# LowduinoPTH_ZIF.net
KiCad netlist of a schematic drawn in EAGLE
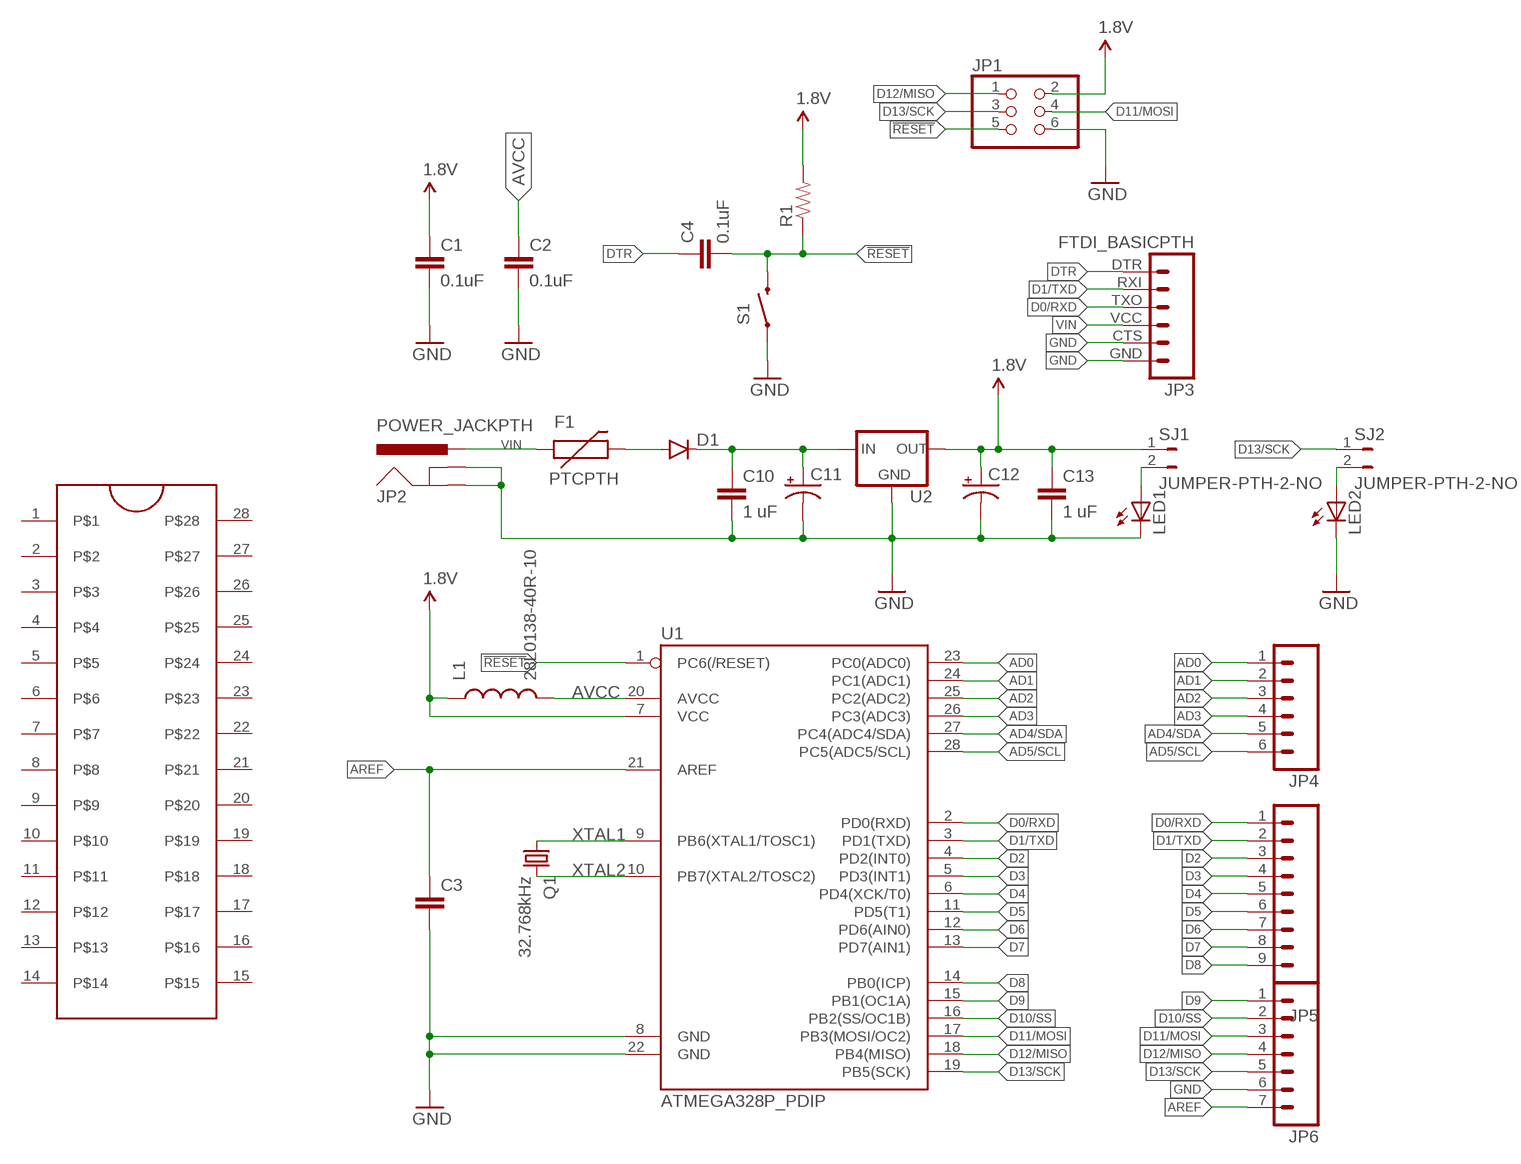
[diagram p0: schematic, sheet 1]

(export (version "E")
  (design (tool "Eeschema 10.0.6"))
  (components
    (comp (ref "C1")
      (value "0.1uF")
      (footprint "eagle-import:CAP-PTH-SMALL2")
      (libsource (lib "eagle-import") (part "CAPPTH2"))
    )
    (comp (ref "C2")
      (value "0.1uF")
      (footprint "eagle-import:CAP-PTH-5MM")
      (libsource (lib "eagle-import") (part "SparkFun-Passives_CAPPTH1"))
    )
    (comp (ref "C3")
      (value "CAPPTH2")
      (footprint "eagle-import:CAP-PTH-SMALL2")
      (libsource (lib "eagle-import") (part "CAPPTH2"))
    )
    (comp (ref "C4")
      (value "0.1uF")
      (footprint "eagle-import:CAP-PTH-SMALL2")
      (libsource (lib "eagle-import") (part "SparkFun-Passives_CAPPTH2"))
    )
    (comp (ref "C10")
      (value "1 uF")
      (footprint "eagle-import:CAP-PTH-SMALL2")
      (libsource (lib "eagle-import") (part "CAPPTH2"))
    )
    (comp (ref "C11")
      (value "CPOL-USE2.5-6")
      (footprint "eagle-import:E2,5-6")
      (libsource (lib "eagle-import") (part "CPOL-USE2.5-6"))
    )
    (comp (ref "C12")
      (value "CPOL-USE2.5-6")
      (footprint "eagle-import:E2,5-6")
      (libsource (lib "eagle-import") (part "CPOL-USE2.5-6"))
    )
    (comp (ref "C13")
      (value "1 uF")
      (footprint "eagle-import:CAP-PTH-SMALL2")
      (libsource (lib "eagle-import") (part "CAPPTH2"))
    )
    (comp (ref "D1")
      (value "DIODEPTH")
      (footprint "eagle-import:DIODE-1N4001")
      (libsource (lib "eagle-import") (part "DIODEPTH"))
    )
    (comp (ref "F1")
      (value "PTCPTH")
      (footprint "eagle-import:PTC")
      (libsource (lib "eagle-import") (part "PTCPTH"))
    )
    (comp (ref "JP1")
      (value "PINHD-2X3")
      (footprint "eagle-import:2X03")
      (libsource (lib "eagle-import") (part "PINHD-2X3"))
    )
    (comp (ref "JP2")
      (value "POWER_JACKPTH")
      (footprint "eagle-import:POWER_JACK_PTH")
      (libsource (lib "eagle-import") (part "POWER_JACKPTH"))
    )
    (comp (ref "JP3")
      (value "FTDI_BASICPTH")
      (footprint "eagle-import:FTDI_BASIC")
      (libsource (lib "eagle-import") (part "FTDI_BASICPTH"))
    )
    (comp (ref "JP4")
      (value "M06SILK_FEMALE_PTH")
      (footprint "eagle-import:1X06")
      (libsource (lib "eagle-import") (part "M06SILK_FEMALE_PTH"))
    )
    (comp (ref "JP5")
      (value "M09")
      (footprint "eagle-import:1X09")
      (libsource (lib "eagle-import") (part "M09"))
    )
    (comp (ref "JP6")
      (value "M07")
      (footprint "eagle-import:1X07")
      (libsource (lib "eagle-import") (part "M07"))
    )
    (comp (ref "L1")
      (value "28L0138-40R-10")
      (footprint "eagle-import:AXIAL-0.6")
      (libsource (lib "eagle-import") (part "INDUCTORAXIAL-0.6"))
    )
    (comp (ref "LED1")
      (value "LED3MM")
      (footprint "eagle-import:LED3MM")
      (libsource (lib "eagle-import") (part "LED3MM"))
    )
    (comp (ref "LED2")
      (value "LED3MM")
      (footprint "eagle-import:LED3MM")
      (libsource (lib "eagle-import") (part "LED3MM"))
    )
    (comp (ref "Q1")
      (value "32.768kHz")
      (footprint "eagle-import:TC26V")
      (libsource (lib "eagle-import") (part "CRYSTALTC26V"))
    )
    (comp (ref "R1")
      (value "RESISTORPTH-1/4W-VERT")
      (footprint "eagle-import:AXIAL-0.1")
      (libsource (lib "eagle-import") (part "RESISTORPTH-1/4W-VERT"))
    )
    (comp (ref "S1")
      (value "SWITCH-MOMENTARY-2PTH")
      (footprint "eagle-import:TACTILE-PTH")
      (libsource (lib "eagle-import") (part "SWITCH-MOMENTARY-2PTH"))
    )
    (comp (ref "SJ1")
      (value "JUMPER-PTH-2-NO")
      (footprint "eagle-import:PTH-JUMPER-2-NO_NO_SILK")
      (libsource (lib "eagle-import") (part "JUMPER-PTH-2-NO"))
    )
    (comp (ref "SJ2")
      (value "JUMPER-PTH-2-NO")
      (footprint "eagle-import:PTH-JUMPER-2-NO_NO_SILK")
      (libsource (lib "eagle-import") (part "JUMPER-PTH-2-NO"))
    )
    (comp (ref "U$1")
      (value "ZIFSOCKET-28-3ZIFFSOCKET-28-3")
      (footprint "eagle-import:DIL28-3-ZIF_SOCKET")
      (libsource (lib "eagle-import") (part "ZIFSOCKET-28-3ZIFFSOCKET-28-3"))
    )
    (comp (ref "U1")
      (value "ATMEGA328P_PDIP")
      (footprint "eagle-import:DIL28-3")
      (libsource (lib "eagle-import") (part "ATMEGA328P_PDIP"))
    )
    (comp (ref "U2")
      (value "V_REG_78XXTO-92_UNTESTED")
      (footprint "eagle-import:TO-92")
      (libsource (lib "eagle-import") (part "V_REG_78XXTO-92_UNTESTED"))
    )
  )
  (nets
    (net (code "1") (name "/XTAL1") (class "Default")
      (node (ref "Q1") (pin "1") (pinfunction "1_1") (pintype "passive"))
      (node (ref "U1") (pin "9") (pinfunction "PB6(XTAL1/TOSC1)_9") (pintype "bidirectional"))
    )
    (net (code "2") (name "/XTAL2") (class "Default")
      (node (ref "Q1") (pin "2") (pinfunction "2_2") (pintype "passive"))
      (node (ref "U1") (pin "10") (pinfunction "PB7(XTAL2/TOSC2)_10") (pintype "bidirectional"))
    )
    (net (code "3") (name "/~{RESET}") (class "Default")
      (node (ref "C4") (pin "2") (pinfunction "2_2") (pintype "passive"))
      (node (ref "JP1") (pin "5") (pinfunction "5_5") (pintype "passive"))
      (node (ref "R1") (pin "P$1") (pinfunction "1_P$1") (pintype "passive"))
      (node (ref "S1") (pin "3") (pinfunction "2_3") (pintype "passive"))
      (node (ref "U1") (pin "1") (pinfunction "PC6(/RESET)_1") (pintype "bidirectional"))
    )
    (net (code "4") (name "1.8V") (class "Default")
      (node (ref "C1") (pin "1") (pinfunction "1_1") (pintype "passive"))
      (node (ref "C12") (pin "+") (pinfunction "+_+") (pintype "passive"))
      (node (ref "C13") (pin "1") (pinfunction "1_1") (pintype "passive"))
      (node (ref "JP1") (pin "2") (pinfunction "2_2") (pintype "passive"))
      (node (ref "L1") (pin "P$1") (pinfunction "1_P$1") (pintype "passive"))
      (node (ref "R1") (pin "P$2") (pinfunction "2_P$2") (pintype "passive"))
      (node (ref "SJ1") (pin "1") (pinfunction "1_1") (pintype "passive"))
      (node (ref "U1") (pin "7") (pinfunction "VCC_7") (pintype "bidirectional"))
      (node (ref "U2") (pin "3") (pinfunction "OUT_3") (pintype "output"))
    )
    (net (code "5") (name "AD0") (class "Default")
      (node (ref "JP4") (pin "1") (pinfunction "1_1") (pintype "passive"))
      (node (ref "U1") (pin "23") (pinfunction "PC0(ADC0)_23") (pintype "bidirectional"))
    )
    (net (code "6") (name "AD1") (class "Default")
      (node (ref "JP4") (pin "2") (pinfunction "2_2") (pintype "passive"))
      (node (ref "U1") (pin "24") (pinfunction "PC1(ADC1)_24") (pintype "bidirectional"))
    )
    (net (code "7") (name "AD2") (class "Default")
      (node (ref "JP4") (pin "3") (pinfunction "3_3") (pintype "passive"))
      (node (ref "U1") (pin "25") (pinfunction "PC2(ADC2)_25") (pintype "bidirectional"))
    )
    (net (code "8") (name "AD3") (class "Default")
      (node (ref "JP4") (pin "4") (pinfunction "4_4") (pintype "passive"))
      (node (ref "U1") (pin "26") (pinfunction "PC3(ADC3)_26") (pintype "bidirectional"))
    )
    (net (code "9") (name "AD4{slash}SDA") (class "Default")
      (node (ref "JP4") (pin "5") (pinfunction "5_5") (pintype "passive"))
      (node (ref "U1") (pin "27") (pinfunction "PC4(ADC4/SDA)_27") (pintype "bidirectional"))
    )
    (net (code "10") (name "AD5{slash}SCL") (class "Default")
      (node (ref "JP4") (pin "6") (pinfunction "6_6") (pintype "passive"))
      (node (ref "U1") (pin "28") (pinfunction "PC5(ADC5/SCL)_28") (pintype "bidirectional"))
    )
    (net (code "11") (name "AREF") (class "Default")
      (node (ref "C3") (pin "1") (pinfunction "1_1") (pintype "passive"))
      (node (ref "JP6") (pin "7") (pinfunction "7_7") (pintype "passive"))
      (node (ref "U1") (pin "21") (pinfunction "AREF_21") (pintype "bidirectional"))
    )
    (net (code "12") (name "AVCC") (class "Default")
      (node (ref "C2") (pin "1") (pinfunction "1_1") (pintype "passive"))
      (node (ref "L1") (pin "P$2") (pinfunction "2_P$2") (pintype "passive"))
      (node (ref "U1") (pin "20") (pinfunction "AVCC_20") (pintype "bidirectional"))
    )
    (net (code "13") (name "D0{slash}RXD") (class "Default")
      (node (ref "JP3") (pin "TXO") (pinfunction "3_TXO") (pintype "passive"))
      (node (ref "JP5") (pin "1") (pinfunction "1_1") (pintype "passive"))
      (node (ref "U1") (pin "2") (pinfunction "PD0(RXD)_2") (pintype "bidirectional"))
    )
    (net (code "14") (name "D1{slash}TXD") (class "Default")
      (node (ref "JP3") (pin "RXI") (pinfunction "2_RXI") (pintype "passive"))
      (node (ref "JP5") (pin "2") (pinfunction "2_2") (pintype "passive"))
      (node (ref "U1") (pin "3") (pinfunction "PD1(TXD)_3") (pintype "bidirectional"))
    )
    (net (code "15") (name "D2") (class "Default")
      (node (ref "JP5") (pin "3") (pinfunction "3_3") (pintype "passive"))
      (node (ref "U1") (pin "4") (pinfunction "PD2(INT0)_4") (pintype "bidirectional"))
    )
    (net (code "16") (name "D3") (class "Default")
      (node (ref "JP5") (pin "4") (pinfunction "4_4") (pintype "passive"))
      (node (ref "U1") (pin "5") (pinfunction "PD3(INT1)_5") (pintype "bidirectional"))
    )
    (net (code "17") (name "D4") (class "Default")
      (node (ref "JP5") (pin "5") (pinfunction "5_5") (pintype "passive"))
      (node (ref "U1") (pin "6") (pinfunction "PD4(XCK/T0)_6") (pintype "bidirectional"))
    )
    (net (code "18") (name "D5") (class "Default")
      (node (ref "JP5") (pin "6") (pinfunction "6_6") (pintype "passive"))
      (node (ref "U1") (pin "11") (pinfunction "PD5(T1)_11") (pintype "bidirectional"))
    )
    (net (code "19") (name "D6") (class "Default")
      (node (ref "JP5") (pin "7") (pinfunction "7_7") (pintype "passive"))
      (node (ref "U1") (pin "12") (pinfunction "PD6(AIN0)_12") (pintype "bidirectional"))
    )
    (net (code "20") (name "D7") (class "Default")
      (node (ref "JP5") (pin "8") (pinfunction "8_8") (pintype "passive"))
      (node (ref "U1") (pin "13") (pinfunction "PD7(AIN1)_13") (pintype "bidirectional"))
    )
    (net (code "21") (name "D8") (class "Default")
      (node (ref "JP5") (pin "9") (pinfunction "9_9") (pintype "passive"))
      (node (ref "U1") (pin "14") (pinfunction "PB0(ICP)_14") (pintype "bidirectional"))
    )
    (net (code "22") (name "D9") (class "Default")
      (node (ref "JP6") (pin "1") (pinfunction "1_1") (pintype "passive"))
      (node (ref "U1") (pin "15") (pinfunction "PB1(OC1A)_15") (pintype "bidirectional"))
    )
    (net (code "23") (name "D10{slash}SS") (class "Default")
      (node (ref "JP6") (pin "2") (pinfunction "2_2") (pintype "passive"))
      (node (ref "U1") (pin "16") (pinfunction "PB2(SS/OC1B)_16") (pintype "bidirectional"))
    )
    (net (code "24") (name "D11{slash}MOSI") (class "Default")
      (node (ref "JP1") (pin "4") (pinfunction "4_4") (pintype "passive"))
      (node (ref "JP6") (pin "3") (pinfunction "3_3") (pintype "passive"))
      (node (ref "U1") (pin "17") (pinfunction "PB3(MOSI/OC2)_17") (pintype "bidirectional"))
    )
    (net (code "25") (name "D12{slash}MISO") (class "Default")
      (node (ref "JP1") (pin "1") (pinfunction "1_1") (pintype "passive"))
      (node (ref "JP6") (pin "4") (pinfunction "4_4") (pintype "passive"))
      (node (ref "U1") (pin "18") (pinfunction "PB4(MISO)_18") (pintype "bidirectional"))
    )
    (net (code "26") (name "D13{slash}SCK") (class "Default")
      (node (ref "JP1") (pin "3") (pinfunction "3_3") (pintype "passive"))
      (node (ref "JP6") (pin "5") (pinfunction "5_5") (pintype "passive"))
      (node (ref "SJ2") (pin "1") (pinfunction "1_1") (pintype "passive"))
      (node (ref "U1") (pin "19") (pinfunction "PB5(SCK)_19") (pintype "bidirectional"))
    )
    (net (code "27") (name "DTR") (class "Default")
      (node (ref "C4") (pin "1") (pinfunction "1_1") (pintype "passive"))
      (node (ref "JP3") (pin "DTR") (pinfunction "1_DTR") (pintype "passive"))
    )
    (net (code "28") (name "GND") (class "Default")
      (node (ref "C1") (pin "2") (pinfunction "2_2") (pintype "passive"))
      (node (ref "C10") (pin "2") (pinfunction "2_2") (pintype "passive"))
      (node (ref "C11") (pin "-") (pinfunction "-_-") (pintype "passive"))
      (node (ref "C12") (pin "-") (pinfunction "-_-") (pintype "passive"))
      (node (ref "C13") (pin "2") (pinfunction "2_2") (pintype "passive"))
      (node (ref "C2") (pin "2") (pinfunction "2_2") (pintype "passive"))
      (node (ref "C3") (pin "2") (pinfunction "2_2") (pintype "passive"))
      (node (ref "JP1") (pin "6") (pinfunction "6_6") (pintype "passive"))
      (node (ref "JP2") (pin "GND") (pinfunction "GND_GND") (pintype "bidirectional"))
      (node (ref "JP2") (pin "GNDBREAK") (pinfunction "GNDBREAK_GNDBREAK") (pintype "bidirectional"))
      (node (ref "JP3") (pin "CTS") (pinfunction "5_CTS") (pintype "passive"))
      (node (ref "JP3") (pin "GND") (pinfunction "6_GND") (pintype "passive"))
      (node (ref "JP6") (pin "6") (pinfunction "6_6") (pintype "passive"))
      (node (ref "LED1") (pin "K") (pinfunction "C_K") (pintype "passive"))
      (node (ref "LED2") (pin "K") (pinfunction "C_K") (pintype "passive"))
      (node (ref "S1") (pin "1") (pinfunction "1_1") (pintype "passive"))
      (node (ref "U1") (pin "22") (pinfunction "GND_22") (pintype "bidirectional"))
      (node (ref "U1") (pin "8") (pinfunction "GND_8") (pintype "bidirectional"))
      (node (ref "U2") (pin "1") (pinfunction "GND_1") (pintype "input"))
    )
    (net (code "29") (name "Net-(F1-2)") (class "Default")
      (node (ref "D1") (pin "A") (pinfunction "A_A") (pintype "passive"))
      (node (ref "F1") (pin "P$2") (pinfunction "2_P$2") (pintype "bidirectional"))
    )
    (net (code "30") (name "Net-(LED1-PadA)") (class "Default")
      (node (ref "LED1") (pin "A") (pinfunction "A_A") (pintype "passive"))
      (node (ref "SJ1") (pin "2") (pinfunction "2_2") (pintype "passive"))
    )
    (net (code "31") (name "Net-(LED2-PadA)") (class "Default")
      (node (ref "LED2") (pin "A") (pinfunction "A_A") (pintype "passive"))
      (node (ref "SJ2") (pin "2") (pinfunction "2_2") (pintype "passive"))
    )
    (net (code "32") (name "Net-(U2-IN)") (class "Default")
      (node (ref "C10") (pin "1") (pinfunction "1_1") (pintype "passive"))
      (node (ref "C11") (pin "+") (pinfunction "+_+") (pintype "passive"))
      (node (ref "D1") (pin "C") (pinfunction "C_C") (pintype "passive"))
      (node (ref "U2") (pin "2") (pinfunction "IN_2") (pintype "input"))
    )
    (net (code "33") (name "VIN") (class "Default")
      (node (ref "F1") (pin "P$1") (pinfunction "1_P$1") (pintype "bidirectional"))
      (node (ref "JP2") (pin "PWR") (pinfunction "PWR_PWR") (pintype "bidirectional"))
      (node (ref "JP3") (pin "VCC") (pinfunction "4_VCC") (pintype "passive"))
    )
    (net (code "34") (name "unconnected-(U$1-P$1-Pad1)") (class "Default")
      (node (ref "U$1") (pin "1") (pinfunction "P$1_1") (pintype "bidirectional"))
    )
    (net (code "35") (name "unconnected-(U$1-P$2-Pad2)") (class "Default")
      (node (ref "U$1") (pin "2") (pinfunction "P$2_2") (pintype "bidirectional"))
    )
    (net (code "36") (name "unconnected-(U$1-P$3-Pad3)") (class "Default")
      (node (ref "U$1") (pin "3") (pinfunction "P$3_3") (pintype "bidirectional"))
    )
    (net (code "37") (name "unconnected-(U$1-P$4-Pad4)") (class "Default")
      (node (ref "U$1") (pin "4") (pinfunction "P$4_4") (pintype "bidirectional"))
    )
    (net (code "38") (name "unconnected-(U$1-P$5-Pad5)") (class "Default")
      (node (ref "U$1") (pin "5") (pinfunction "P$5_5") (pintype "bidirectional"))
    )
    (net (code "39") (name "unconnected-(U$1-P$6-Pad6)") (class "Default")
      (node (ref "U$1") (pin "6") (pinfunction "P$6_6") (pintype "bidirectional"))
    )
    (net (code "40") (name "unconnected-(U$1-P$7-Pad7)") (class "Default")
      (node (ref "U$1") (pin "7") (pinfunction "P$7_7") (pintype "bidirectional"))
    )
    (net (code "41") (name "unconnected-(U$1-P$8-Pad8)") (class "Default")
      (node (ref "U$1") (pin "8") (pinfunction "P$8_8") (pintype "bidirectional"))
    )
    (net (code "42") (name "unconnected-(U$1-P$9-Pad9)") (class "Default")
      (node (ref "U$1") (pin "9") (pinfunction "P$9_9") (pintype "bidirectional"))
    )
    (net (code "43") (name "unconnected-(U$1-P$10-Pad10)") (class "Default")
      (node (ref "U$1") (pin "10") (pinfunction "P$10_10") (pintype "bidirectional"))
    )
    (net (code "44") (name "unconnected-(U$1-P$11-Pad11)") (class "Default")
      (node (ref "U$1") (pin "11") (pinfunction "P$11_11") (pintype "bidirectional"))
    )
    (net (code "45") (name "unconnected-(U$1-P$12-Pad12)") (class "Default")
      (node (ref "U$1") (pin "12") (pinfunction "P$12_12") (pintype "bidirectional"))
    )
    (net (code "46") (name "unconnected-(U$1-P$13-Pad13)") (class "Default")
      (node (ref "U$1") (pin "13") (pinfunction "P$13_13") (pintype "bidirectional"))
    )
    (net (code "47") (name "unconnected-(U$1-P$14-Pad14)") (class "Default")
      (node (ref "U$1") (pin "14") (pinfunction "P$14_14") (pintype "bidirectional"))
    )
    (net (code "48") (name "unconnected-(U$1-P$15-Pad15)") (class "Default")
      (node (ref "U$1") (pin "15") (pinfunction "P$15_15") (pintype "bidirectional"))
    )
    (net (code "49") (name "unconnected-(U$1-P$16-Pad16)") (class "Default")
      (node (ref "U$1") (pin "16") (pinfunction "P$16_16") (pintype "bidirectional"))
    )
    (net (code "50") (name "unconnected-(U$1-P$17-Pad17)") (class "Default")
      (node (ref "U$1") (pin "17") (pinfunction "P$17_17") (pintype "bidirectional"))
    )
    (net (code "51") (name "unconnected-(U$1-P$18-Pad18)") (class "Default")
      (node (ref "U$1") (pin "18") (pinfunction "P$18_18") (pintype "bidirectional"))
    )
    (net (code "52") (name "unconnected-(U$1-P$19-Pad19)") (class "Default")
      (node (ref "U$1") (pin "19") (pinfunction "P$19_19") (pintype "bidirectional"))
    )
    (net (code "53") (name "unconnected-(U$1-P$20-Pad20)") (class "Default")
      (node (ref "U$1") (pin "20") (pinfunction "P$20_20") (pintype "bidirectional"))
    )
    (net (code "54") (name "unconnected-(U$1-P$21-Pad21)") (class "Default")
      (node (ref "U$1") (pin "21") (pinfunction "P$21_21") (pintype "bidirectional"))
    )
    (net (code "55") (name "unconnected-(U$1-P$22-Pad22)") (class "Default")
      (node (ref "U$1") (pin "22") (pinfunction "P$22_22") (pintype "bidirectional"))
    )
    (net (code "56") (name "unconnected-(U$1-P$23-Pad23)") (class "Default")
      (node (ref "U$1") (pin "23") (pinfunction "P$23_23") (pintype "bidirectional"))
    )
    (net (code "57") (name "unconnected-(U$1-P$24-Pad24)") (class "Default")
      (node (ref "U$1") (pin "24") (pinfunction "P$24_24") (pintype "bidirectional"))
    )
    (net (code "58") (name "unconnected-(U$1-P$25-Pad25)") (class "Default")
      (node (ref "U$1") (pin "25") (pinfunction "P$25_25") (pintype "bidirectional"))
    )
    (net (code "59") (name "unconnected-(U$1-P$26-Pad26)") (class "Default")
      (node (ref "U$1") (pin "26") (pinfunction "P$26_26") (pintype "bidirectional"))
    )
    (net (code "60") (name "unconnected-(U$1-P$27-Pad27)") (class "Default")
      (node (ref "U$1") (pin "27") (pinfunction "P$27_27") (pintype "bidirectional"))
    )
    (net (code "61") (name "unconnected-(U$1-P$28-Pad28)") (class "Default")
      (node (ref "U$1") (pin "28") (pinfunction "P$28_28") (pintype "bidirectional"))
    )
  )
)
